# Thetis_RevD1_SCH.net
KiCad netlist of a schematic drawn in EAGLE
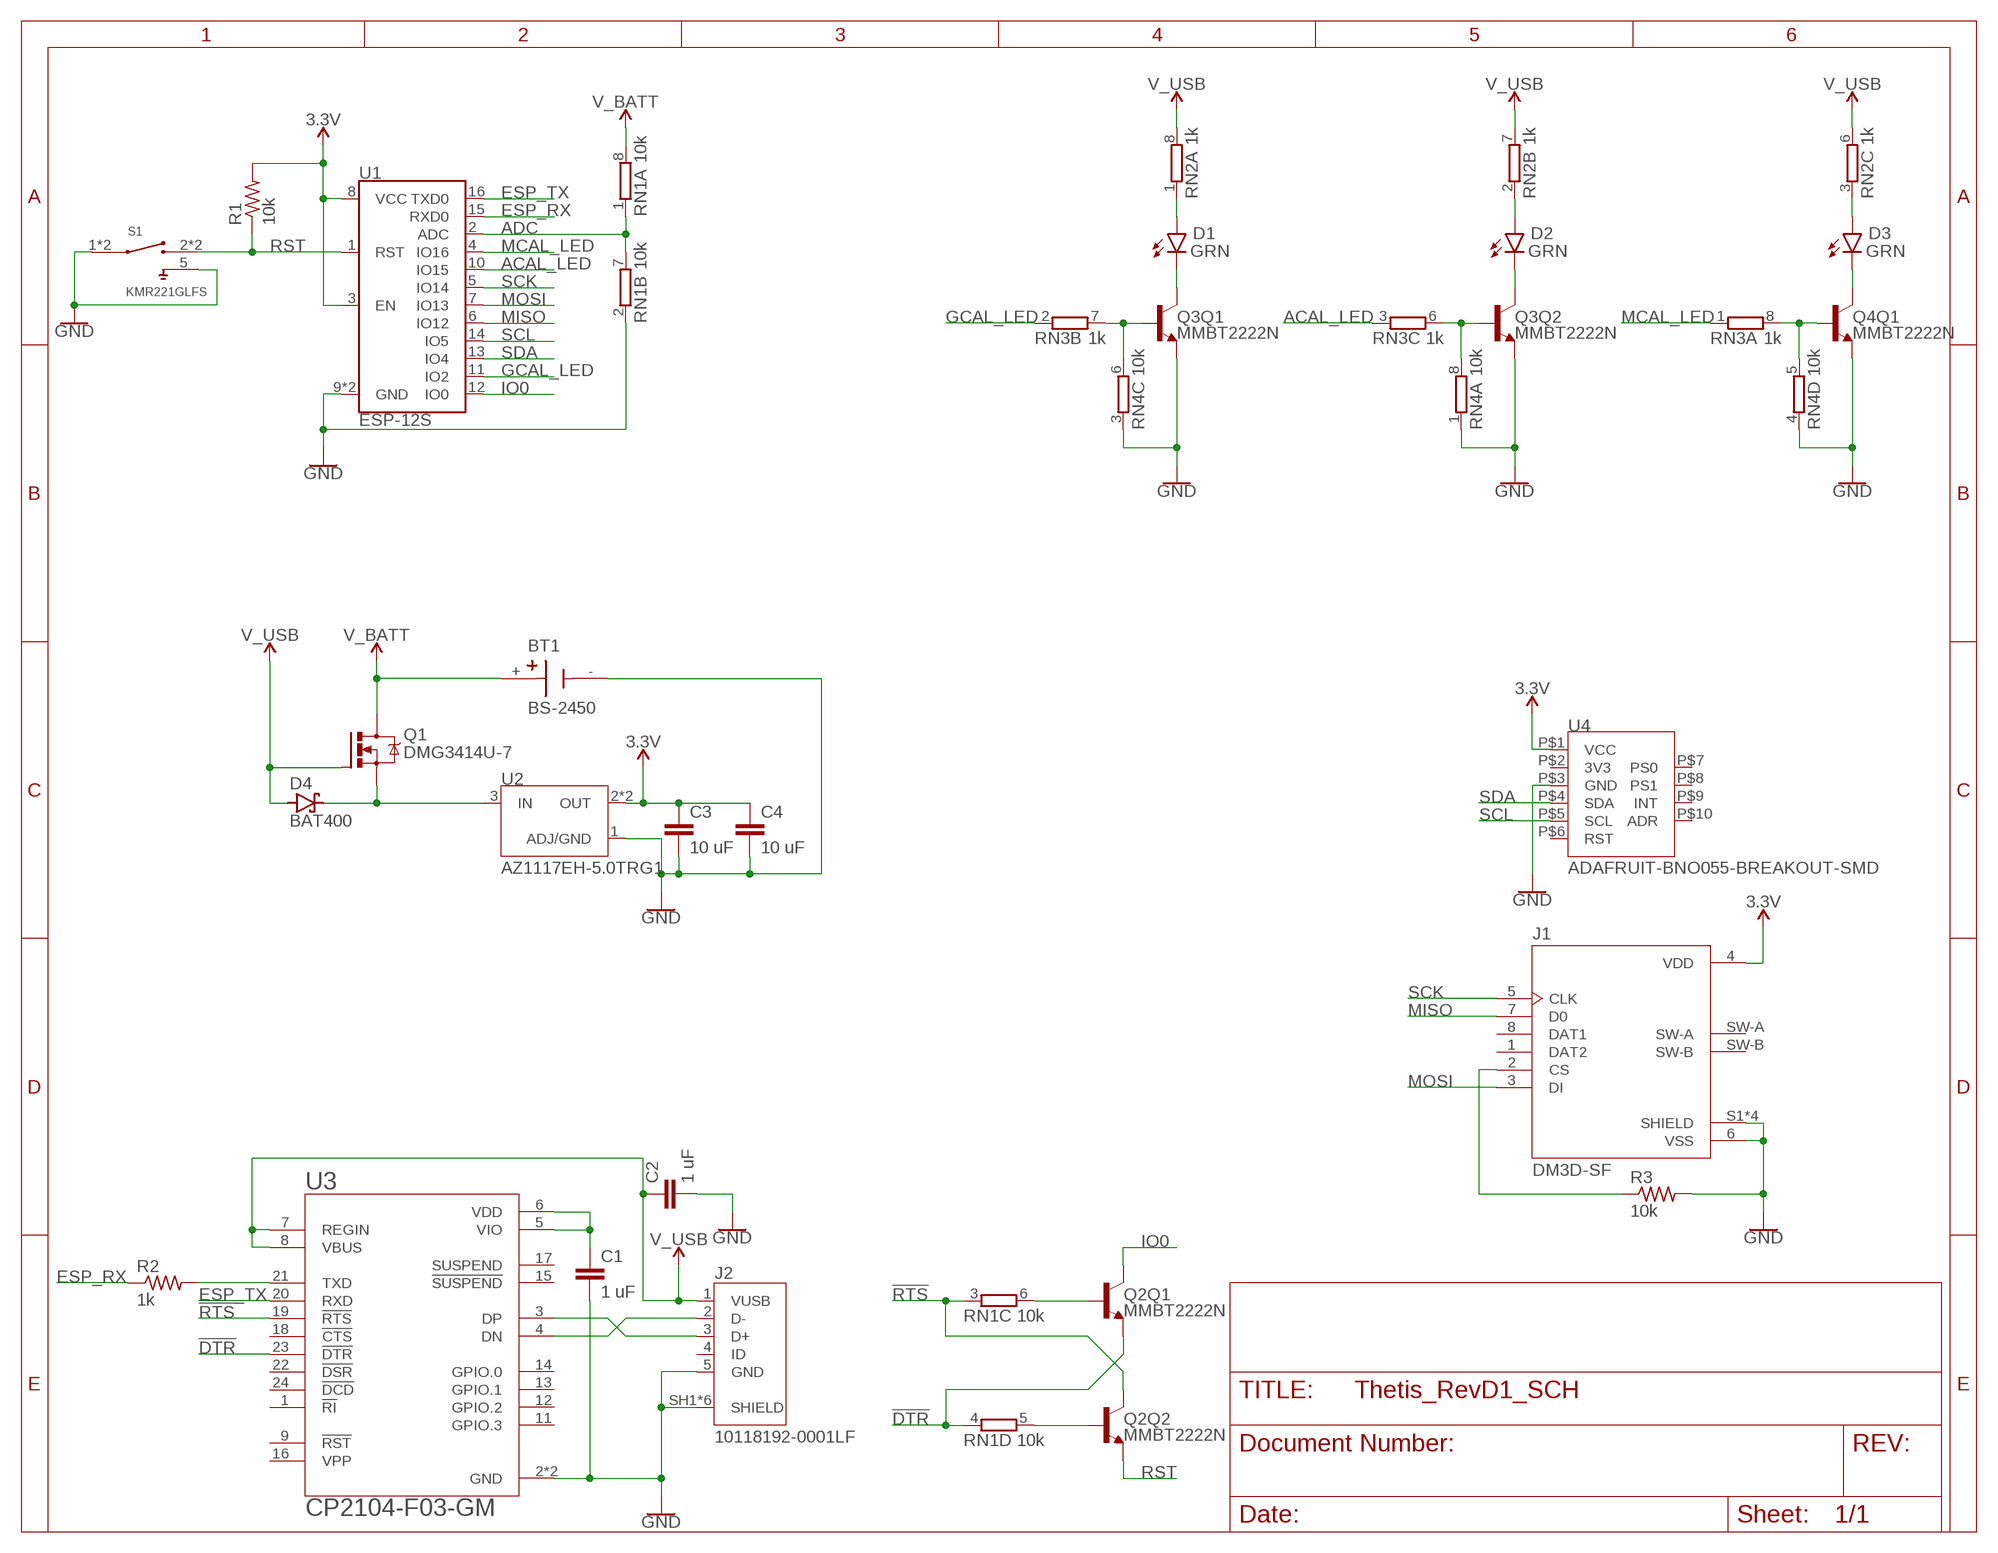
[diagram p0: schematic, sheet 1]

(export (version "E")
  (design (tool "Eeschema 10.0.6"))
  (components
    (comp (ref "BT1")
      (value "BS-2450")
      (footprint "eagle-import:BAT_BS-2450")
      (fields (field (name "MF") "MPD"))
      (libsource (lib "eagle-import") (part "BS-2450"))
    )
    (comp (ref "C1")
      (value "1 uF")
      (footprint "eagle-import:C0603")
      (libsource (lib "eagle-import") (part "C-EUC0603"))
    )
    (comp (ref "C2")
      (value "1 uF")
      (footprint "eagle-import:C0603")
      (libsource (lib "eagle-import") (part "C-EUC0603"))
    )
    (comp (ref "C3")
      (value "10 uF")
      (footprint "eagle-import:C0603")
      (libsource (lib "eagle-import") (part "C-EUC0603"))
    )
    (comp (ref "C4")
      (value "10 uF")
      (footprint "eagle-import:C0603")
      (libsource (lib "eagle-import") (part "C-EUC0603"))
    )
    (comp (ref "D1")
      (value "GRN")
      (footprint "eagle-import:LEDC1608X65N")
      (libsource (lib "eagle-import") (part "CHIP-ROUND-G_0603"))
    )
    (comp (ref "D2")
      (value "GRN")
      (footprint "eagle-import:LEDC1608X65N")
      (libsource (lib "eagle-import") (part "CHIP-ROUND-G_0603"))
    )
    (comp (ref "D3")
      (value "GRN")
      (footprint "eagle-import:LEDC1608X65N")
      (libsource (lib "eagle-import") (part "CHIP-ROUND-G_0603"))
    )
    (comp (ref "D4")
      (value "BAT400")
      (footprint "eagle-import:SOT23")
      (libsource (lib "eagle-import") (part "BAS40"))
    )
    (comp (ref "J1")
      (value "DM3D-SF")
      (footprint "eagle-import:HRS_DM3D-SF")
      (fields (field (name "MANUFACTURER") "Hirose"))
      (libsource (lib "eagle-import") (part "DM3D-SF"))
    )
    (comp (ref "J2")
      (value "10118192-0001LF")
      (footprint "eagle-import:AMPHENOL_10118192-0001LF")
      (fields (field (name "MANUFACTURER") "Amphenol"))
      (libsource (lib "eagle-import") (part "10118192-0001LF"))
    )
    (comp (ref "Q1")
      (value "DMG3414U-7")
      (footprint "eagle-import:SOT23")
      (libsource (lib "eagle-import") (part "NMOSFETSOT23"))
    )
    (comp (ref "Q2")
      (value "MMBT2222N")
      (footprint "eagle-import:SC70-6")
      (libsource (lib "eagle-import") (part "TRANS_NPN_DUAL-MBT3904DW1T1"))
    )
    (comp (ref "Q3")
      (value "MMBT2222N")
      (footprint "eagle-import:SC70-6")
      (libsource (lib "eagle-import") (part "TRANS_NPN_DUAL-MBT3904DW1T1"))
    )
    (comp (ref "Q4")
      (value "MMBT2222N")
      (footprint "eagle-import:SC70-6")
      (libsource (lib "eagle-import") (part "TRANS_NPN_DUAL-MBT3904DW1T1"))
    )
    (comp (ref "R1")
      (value "10k")
      (footprint "eagle-import:R0603")
      (libsource (lib "eagle-import") (part "R-US_R0603"))
    )
    (comp (ref "R2")
      (value "1k")
      (footprint "eagle-import:R0603")
      (libsource (lib "eagle-import") (part "R-US_R0603"))
    )
    (comp (ref "R3")
      (value "10k")
      (footprint "eagle-import:R0603")
      (libsource (lib "eagle-import") (part "R-US_R0603"))
    )
    (comp (ref "RN1")
      (value "10k")
      (footprint "eagle-import:EXB28V")
      (libsource (lib "eagle-import") (part "4R-NEXB28V"))
    )
    (comp (ref "RN2")
      (value "1k")
      (footprint "eagle-import:EXB28V")
      (libsource (lib "eagle-import") (part "4R-NEXB28V"))
    )
    (comp (ref "RN3")
      (value "1k")
      (footprint "eagle-import:EXB28V")
      (libsource (lib "eagle-import") (part "4R-NEXB28V"))
    )
    (comp (ref "RN4")
      (value "10k")
      (footprint "eagle-import:EXB28V")
      (libsource (lib "eagle-import") (part "4R-NEXB28V"))
    )
    (comp (ref "S1")
      (value "KMR221GLFS")
      (footprint "eagle-import:SW_KMR221GLFS")
      (fields (field (name "MANUFACTURER") "CnK"))
      (libsource (lib "eagle-import") (part "KMR221GLFS"))
    )
    (comp (ref "U1")
      (value "ESP-12S")
      (footprint "eagle-import:ESP-12S")
      (libsource (lib "eagle-import") (part "ESP-12S"))
    )
    (comp (ref "U2")
      (value "AZ1117EH-5.0TRG1")
      (footprint "eagle-import:SOT230P700X180-4N")
      (fields (field (name "MF") "Diodes Inc."))
      (libsource (lib "eagle-import") (part "AZ1117EH-5.0TRG1"))
    )
    (comp (ref "U3")
      (value "CP2104-F03-GM")
      (footprint "eagle-import:QFN50P400X400X80-25N")
      (libsource (lib "eagle-import") (part "CP2104-F03-GM"))
    )
    (comp (ref "U4")
      (value "ADAFRUIT-BNO055-BREAKOUT-SMD")
      (footprint "eagle-import:ADAFRUIT-BNO055-BREAKOUT-SMD")
      (libsource (lib "eagle-import") (part "ADAFRUIT-BNO055-BREAKOUT-SMD"))
    )
  )
  (nets
    (net (code "1") (name "/3V3") (class "Default")
      (node (ref "U4") (pin "P$2") (pinfunction "3V3_P$2") (pintype "power_in"))
    )
    (net (code "2") (name "/ACAL_LED") (class "Default")
      (node (ref "RN3") (pin "3") (pinfunction "1_3") (pintype "passive"))
      (node (ref "U1") (pin "10") (pinfunction "IO15_10") (pintype "bidirectional"))
    )
    (net (code "3") (name "/ADC") (class "Default")
      (node (ref "RN1") (pin "1") (pinfunction "1_1") (pintype "passive"))
      (node (ref "RN1") (pin "7") (pinfunction "2_7") (pintype "passive"))
      (node (ref "U1") (pin "2") (pinfunction "ADC_2") (pintype "bidirectional"))
    )
    (net (code "4") (name "/ESP_RX") (class "Default")
      (node (ref "R2") (pin "1") (pinfunction "1_1") (pintype "passive"))
      (node (ref "U1") (pin "15") (pinfunction "RXD0_15") (pintype "bidirectional"))
    )
    (net (code "5") (name "/ESP_TX") (class "Default")
      (node (ref "U1") (pin "16") (pinfunction "TXD0_16") (pintype "bidirectional"))
      (node (ref "U3") (pin "20") (pinfunction "RXD_20") (pintype "input"))
    )
    (net (code "6") (name "/GCAL_LED") (class "Default")
      (node (ref "RN3") (pin "2") (pinfunction "1_2") (pintype "passive"))
      (node (ref "U1") (pin "11") (pinfunction "IO2_11") (pintype "bidirectional"))
    )
    (net (code "7") (name "/IO0") (class "Default")
      (node (ref "Q2") (pin "3") (pinfunction "C_3") (pintype "passive"))
      (node (ref "U1") (pin "12") (pinfunction "IO0_12") (pintype "bidirectional"))
    )
    (net (code "8") (name "/MCAL_LED") (class "Default")
      (node (ref "RN3") (pin "1") (pinfunction "1_1") (pintype "passive"))
      (node (ref "U1") (pin "4") (pinfunction "IO16_4") (pintype "bidirectional"))
    )
    (net (code "9") (name "/MISO") (class "Default")
      (node (ref "J1") (pin "7") (pinfunction "D0_7") (pintype "bidirectional"))
      (node (ref "U1") (pin "6") (pinfunction "IO12_6") (pintype "bidirectional"))
    )
    (net (code "10") (name "/MOSI") (class "Default")
      (node (ref "J1") (pin "3") (pinfunction "DI_3") (pintype "bidirectional"))
      (node (ref "U1") (pin "7") (pinfunction "IO13_7") (pintype "bidirectional"))
    )
    (net (code "11") (name "/RST") (class "Default")
      (node (ref "Q2") (pin "1") (pinfunction "E_1") (pintype "passive"))
      (node (ref "R1") (pin "1") (pinfunction "1_1") (pintype "passive"))
      (node (ref "S1") (pin "2") (pinfunction "3_2") (pintype "passive"))
      (node (ref "S1") (pin "3") (pinfunction "3_3") (pintype "passive"))
      (node (ref "U1") (pin "1") (pinfunction "RST_1") (pintype "bidirectional"))
    )
    (net (code "12") (name "/SCK") (class "Default")
      (node (ref "J1") (pin "5") (pinfunction "CLK_5") (pintype "bidirectional"))
      (node (ref "U1") (pin "5") (pinfunction "IO14_5") (pintype "bidirectional"))
    )
    (net (code "13") (name "/SCL") (class "Default")
      (node (ref "U1") (pin "14") (pinfunction "IO5_14") (pintype "bidirectional"))
      (node (ref "U4") (pin "P$5") (pinfunction "SCL_P$5") (pintype "bidirectional"))
    )
    (net (code "14") (name "/SDA") (class "Default")
      (node (ref "U1") (pin "13") (pinfunction "IO4_13") (pintype "bidirectional"))
      (node (ref "U4") (pin "P$4") (pinfunction "SDA_P$4") (pintype "bidirectional"))
    )
    (net (code "15") (name "/~{DTR}") (class "Default")
      (node (ref "Q2") (pin "4") (pinfunction "E_4") (pintype "passive"))
      (node (ref "RN1") (pin "4") (pinfunction "1_4") (pintype "passive"))
      (node (ref "U3") (pin "23") (pinfunction "~{DTR}_23") (pintype "output"))
    )
    (net (code "16") (name "/~{RTS}") (class "Default")
      (node (ref "Q2") (pin "6") (pinfunction "C_6") (pintype "passive"))
      (node (ref "RN1") (pin "3") (pinfunction "1_3") (pintype "passive"))
      (node (ref "U3") (pin "19") (pinfunction "~{RTS}_19") (pintype "output"))
    )
    (net (code "17") (name "3.3V") (class "Default")
      (node (ref "C3") (pin "1") (pinfunction "1_1") (pintype "passive"))
      (node (ref "C4") (pin "1") (pinfunction "1_1") (pintype "passive"))
      (node (ref "J1") (pin "4") (pinfunction "VDD_4") (pintype "power_in"))
      (node (ref "R1") (pin "2") (pinfunction "2_2") (pintype "passive"))
      (node (ref "U1") (pin "3") (pinfunction "EN_3") (pintype "bidirectional"))
      (node (ref "U1") (pin "8") (pinfunction "VCC_8") (pintype "bidirectional"))
      (node (ref "U2") (pin "2") (pinfunction "OUT_2") (pintype "output"))
      (node (ref "U2") (pin "4") (pinfunction "OUT_4") (pintype "output"))
      (node (ref "U4") (pin "P$1") (pinfunction "VCC_P$1") (pintype "power_in"))
    )
    (net (code "18") (name "GND") (class "Default")
      (node (ref "BT1") (pin "-") (pinfunction "-_-") (pintype "passive"))
      (node (ref "C1") (pin "2") (pinfunction "2_2") (pintype "passive"))
      (node (ref "C2") (pin "2") (pinfunction "2_2") (pintype "passive"))
      (node (ref "C3") (pin "2") (pinfunction "2_2") (pintype "passive"))
      (node (ref "C4") (pin "2") (pinfunction "2_2") (pintype "passive"))
      (node (ref "J1") (pin "6") (pinfunction "VSS_6") (pintype "power_in"))
      (node (ref "J1") (pin "S1") (pinfunction "SHIELD_S1") (pintype "passive"))
      (node (ref "J1") (pin "S2") (pinfunction "SHIELD_S2") (pintype "passive"))
      (node (ref "J1") (pin "S3") (pinfunction "SHIELD_S3") (pintype "passive"))
      (node (ref "J1") (pin "S4") (pinfunction "SHIELD_S4") (pintype "passive"))
      (node (ref "J2") (pin "5") (pinfunction "GND_5") (pintype "passive"))
      (node (ref "J2") (pin "SH1") (pinfunction "SHIELD_SH1") (pintype "passive"))
      (node (ref "J2") (pin "SH2") (pinfunction "SHIELD_SH2") (pintype "passive"))
      (node (ref "J2") (pin "SH3") (pinfunction "SHIELD_SH3") (pintype "passive"))
      (node (ref "J2") (pin "SH4") (pinfunction "SHIELD_SH4") (pintype "passive"))
      (node (ref "J2") (pin "SH5") (pinfunction "SHIELD_SH5") (pintype "passive"))
      (node (ref "J2") (pin "SH6") (pinfunction "SHIELD_SH6") (pintype "passive"))
      (node (ref "Q3") (pin "1") (pinfunction "E_1") (pintype "passive"))
      (node (ref "Q3") (pin "4") (pinfunction "E_4") (pintype "passive"))
      (node (ref "Q4") (pin "4") (pinfunction "E_4") (pintype "passive"))
      (node (ref "R3") (pin "2") (pinfunction "2_2") (pintype "passive"))
      (node (ref "RN1") (pin "2") (pinfunction "1_2") (pintype "passive"))
      (node (ref "RN4") (pin "1") (pinfunction "1_1") (pintype "passive"))
      (node (ref "RN4") (pin "3") (pinfunction "1_3") (pintype "passive"))
      (node (ref "RN4") (pin "4") (pinfunction "1_4") (pintype "passive"))
      (node (ref "S1") (pin "1") (pinfunction "1_1") (pintype "passive"))
      (node (ref "S1") (pin "4") (pinfunction "1_4") (pintype "passive"))
      (node (ref "S1") (pin "5") (pinfunction "5_5") (pintype "passive"))
      (node (ref "U1") (pin "9") (pinfunction "GND_9") (pintype "bidirectional"))
      (node (ref "U1") (pin "P$1") (pinfunction "GND_P$1") (pintype "bidirectional"))
      (node (ref "U2") (pin "1") (pinfunction "ADJ/GND_1") (pintype "power_in"))
      (node (ref "U3") (pin "2") (pinfunction "GND_2") (pintype "power_in"))
      (node (ref "U3") (pin "25") (pinfunction "GND_25") (pintype "power_in"))
      (node (ref "U4") (pin "P$3") (pinfunction "GND_P$3") (pintype "power_in"))
    )
    (net (code "19") (name "Net-(D1-PadA)") (class "Default")
      (node (ref "D1") (pin "A") (pinfunction "A_A") (pintype "passive"))
      (node (ref "RN2") (pin "1") (pinfunction "1_1") (pintype "passive"))
    )
    (net (code "20") (name "Net-(D4-C)") (class "Default")
      (node (ref "D4") (pin "3") (pinfunction "C_3") (pintype "passive"))
      (node (ref "Q1") (pin "2") (pinfunction "S_2") (pintype "passive"))
      (node (ref "U2") (pin "3") (pinfunction "IN_3") (pintype "input"))
    )
    (net (code "21") (name "Net-(J1-CS)") (class "Default")
      (node (ref "J1") (pin "2") (pinfunction "CS_2") (pintype "bidirectional"))
      (node (ref "R3") (pin "1") (pinfunction "1_1") (pintype "passive"))
    )
    (net (code "22") (name "Net-(J2-D+)") (class "Default")
      (node (ref "J2") (pin "3") (pinfunction "D+_3") (pintype "passive"))
      (node (ref "U3") (pin "3") (pinfunction "DP_3") (pintype "bidirectional"))
    )
    (net (code "23") (name "Net-(J2-D-)") (class "Default")
      (node (ref "J2") (pin "2") (pinfunction "D-_2") (pintype "passive"))
      (node (ref "U3") (pin "4") (pinfunction "DN_4") (pintype "bidirectional"))
    )
    (net (code "24") (name "Net-(Q2A-B)") (class "Default")
      (node (ref "Q2") (pin "5") (pinfunction "B_5") (pintype "passive"))
      (node (ref "RN1") (pin "6") (pinfunction "2_6") (pintype "passive"))
    )
    (net (code "25") (name "Net-(Q2B-B)") (class "Default")
      (node (ref "Q2") (pin "2") (pinfunction "B_2") (pintype "passive"))
      (node (ref "RN1") (pin "5") (pinfunction "2_5") (pintype "passive"))
    )
    (net (code "26") (name "Net-(Q3A-B)") (class "Default")
      (node (ref "Q3") (pin "5") (pinfunction "B_5") (pintype "passive"))
      (node (ref "RN3") (pin "7") (pinfunction "2_7") (pintype "passive"))
      (node (ref "RN4") (pin "6") (pinfunction "2_6") (pintype "passive"))
    )
    (net (code "27") (name "Net-(Q3A-C)") (class "Default")
      (node (ref "D1") (pin "C") (pinfunction "C_C") (pintype "passive"))
      (node (ref "Q3") (pin "3") (pinfunction "C_3") (pintype "passive"))
    )
    (net (code "28") (name "Net-(Q3B-B)") (class "Default")
      (node (ref "Q3") (pin "2") (pinfunction "B_2") (pintype "passive"))
      (node (ref "RN3") (pin "6") (pinfunction "2_6") (pintype "passive"))
      (node (ref "RN4") (pin "8") (pinfunction "2_8") (pintype "passive"))
    )
    (net (code "29") (name "Net-(Q3B-C)") (class "Default")
      (node (ref "D2") (pin "C") (pinfunction "C_C") (pintype "passive"))
      (node (ref "Q3") (pin "6") (pinfunction "C_6") (pintype "passive"))
    )
    (net (code "30") (name "Net-(Q4A-B)") (class "Default")
      (node (ref "Q4") (pin "5") (pinfunction "B_5") (pintype "passive"))
      (node (ref "RN3") (pin "8") (pinfunction "2_8") (pintype "passive"))
      (node (ref "RN4") (pin "5") (pinfunction "2_5") (pintype "passive"))
    )
    (net (code "31") (name "Net-(Q4A-C)") (class "Default")
      (node (ref "D3") (pin "C") (pinfunction "C_C") (pintype "passive"))
      (node (ref "Q4") (pin "3") (pinfunction "C_3") (pintype "passive"))
    )
    (net (code "32") (name "Net-(RN2B-1)") (class "Default")
      (node (ref "D2") (pin "A") (pinfunction "A_A") (pintype "passive"))
      (node (ref "RN2") (pin "2") (pinfunction "1_2") (pintype "passive"))
    )
    (net (code "33") (name "Net-(RN2C-1)") (class "Default")
      (node (ref "D3") (pin "A") (pinfunction "A_A") (pintype "passive"))
      (node (ref "RN2") (pin "3") (pinfunction "1_3") (pintype "passive"))
    )
    (net (code "34") (name "Net-(U3-TXD)") (class "Default")
      (node (ref "R2") (pin "2") (pinfunction "2_2") (pintype "passive"))
      (node (ref "U3") (pin "21") (pinfunction "TXD_21") (pintype "output"))
    )
    (net (code "35") (name "Net-(U3-VDD)") (class "Default")
      (node (ref "C1") (pin "1") (pinfunction "1_1") (pintype "passive"))
      (node (ref "U3") (pin "5") (pinfunction "VIO_5") (pintype "power_in"))
      (node (ref "U3") (pin "6") (pinfunction "VDD_6") (pintype "power_in"))
    )
    (net (code "36") (name "V_BATT") (class "Default")
      (node (ref "BT1") (pin "+") (pinfunction "+_+") (pintype "passive"))
      (node (ref "Q1") (pin "3") (pinfunction "D_3") (pintype "passive"))
      (node (ref "RN1") (pin "8") (pinfunction "2_8") (pintype "passive"))
    )
    (net (code "37") (name "V_USB") (class "Default")
      (node (ref "C2") (pin "1") (pinfunction "1_1") (pintype "passive"))
      (node (ref "D4") (pin "1") (pinfunction "A_1") (pintype "passive"))
      (node (ref "J2") (pin "1") (pinfunction "VUSB_1") (pintype "passive"))
      (node (ref "Q1") (pin "1") (pinfunction "G_1") (pintype "passive"))
      (node (ref "RN2") (pin "6") (pinfunction "2_6") (pintype "passive"))
      (node (ref "RN2") (pin "7") (pinfunction "2_7") (pintype "passive"))
      (node (ref "RN2") (pin "8") (pinfunction "2_8") (pintype "passive"))
      (node (ref "U3") (pin "7") (pinfunction "REGIN_7") (pintype "input"))
      (node (ref "U3") (pin "8") (pinfunction "VBUS_8") (pintype "input"))
    )
    (net (code "38") (name "unconnected-(J1-DAT1-Pad8)") (class "Default")
      (node (ref "J1") (pin "8") (pinfunction "DAT1_8") (pintype "bidirectional"))
    )
    (net (code "39") (name "unconnected-(J1-DAT2-Pad1)") (class "Default")
      (node (ref "J1") (pin "1") (pinfunction "DAT2_1") (pintype "bidirectional"))
    )
    (net (code "40") (name "unconnected-(J1-PadSW-A)") (class "Default")
      (node (ref "J1") (pin "SW-A") (pinfunction "SW-A_SW-A") (pintype "bidirectional"))
    )
    (net (code "41") (name "unconnected-(J1-PadSW-B)") (class "Default")
      (node (ref "J1") (pin "SW-B") (pinfunction "SW-B_SW-B") (pintype "bidirectional"))
    )
    (net (code "42") (name "unconnected-(J2-ID-Pad4)") (class "Default")
      (node (ref "J2") (pin "4") (pinfunction "ID_4") (pintype "passive"))
    )
    (net (code "43") (name "unconnected-(U3-GPIO.0-Pad14)") (class "Default")
      (node (ref "U3") (pin "14") (pinfunction "GPIO.0_14") (pintype "bidirectional"))
    )
    (net (code "44") (name "unconnected-(U3-GPIO.1-Pad13)") (class "Default")
      (node (ref "U3") (pin "13") (pinfunction "GPIO.1_13") (pintype "bidirectional"))
    )
    (net (code "45") (name "unconnected-(U3-GPIO.2-Pad12)") (class "Default")
      (node (ref "U3") (pin "12") (pinfunction "GPIO.2_12") (pintype "bidirectional"))
    )
    (net (code "46") (name "unconnected-(U3-GPIO.3-Pad11)") (class "Default")
      (node (ref "U3") (pin "11") (pinfunction "GPIO.3_11") (pintype "bidirectional"))
    )
    (net (code "47") (name "unconnected-(U3-SUSPEND-Pad17)") (class "Default")
      (node (ref "U3") (pin "17") (pinfunction "SUSPEND_17") (pintype "output"))
    )
    (net (code "48") (name "unconnected-(U3-VPP-Pad16)") (class "Default")
      (node (ref "U3") (pin "16") (pinfunction "VPP_16") (pintype "passive"))
    )
    (net (code "49") (name "unconnected-(U3-~{CTS}-Pad18)") (class "Default")
      (node (ref "U3") (pin "18") (pinfunction "~{CTS}_18") (pintype "input"))
    )
    (net (code "50") (name "unconnected-(U3-~{DCD}-Pad24)") (class "Default")
      (node (ref "U3") (pin "24") (pinfunction "~{DCD}_24") (pintype "input"))
    )
    (net (code "51") (name "unconnected-(U3-~{DSR}-Pad22)") (class "Default")
      (node (ref "U3") (pin "22") (pinfunction "~{DSR}_22") (pintype "input"))
    )
    (net (code "52") (name "unconnected-(U3-~{RI}-Pad1)") (class "Default")
      (node (ref "U3") (pin "1") (pinfunction "~{RI}_1") (pintype "input"))
    )
    (net (code "53") (name "unconnected-(U3-~{RST}-Pad9)") (class "Default")
      (node (ref "U3") (pin "9") (pinfunction "~{RST}_9") (pintype "bidirectional"))
    )
    (net (code "54") (name "unconnected-(U3-~{SUSPEND}-Pad15)") (class "Default")
      (node (ref "U3") (pin "15") (pinfunction "~{SUSPEND}_15") (pintype "output"))
    )
    (net (code "55") (name "unconnected-(U4-ADR-PadP$10)") (class "Default")
      (node (ref "U4") (pin "P$10") (pinfunction "ADR_P$10") (pintype "bidirectional"))
    )
    (net (code "56") (name "unconnected-(U4-INT-PadP$9)") (class "Default")
      (node (ref "U4") (pin "P$9") (pinfunction "INT_P$9") (pintype "bidirectional"))
    )
    (net (code "57") (name "unconnected-(U4-PS0-PadP$7)") (class "Default")
      (node (ref "U4") (pin "P$7") (pinfunction "PS0_P$7") (pintype "bidirectional"))
    )
    (net (code "58") (name "unconnected-(U4-PS1-PadP$8)") (class "Default")
      (node (ref "U4") (pin "P$8") (pinfunction "PS1_P$8") (pintype "bidirectional"))
    )
    (net (code "59") (name "unconnected-(U4-RST-PadP$6)") (class "Default")
      (node (ref "U4") (pin "P$6") (pinfunction "RST_P$6") (pintype "input"))
    )
  )
)
